# MB963.net
KiCad netlist of a schematic drawn in Altium Designer
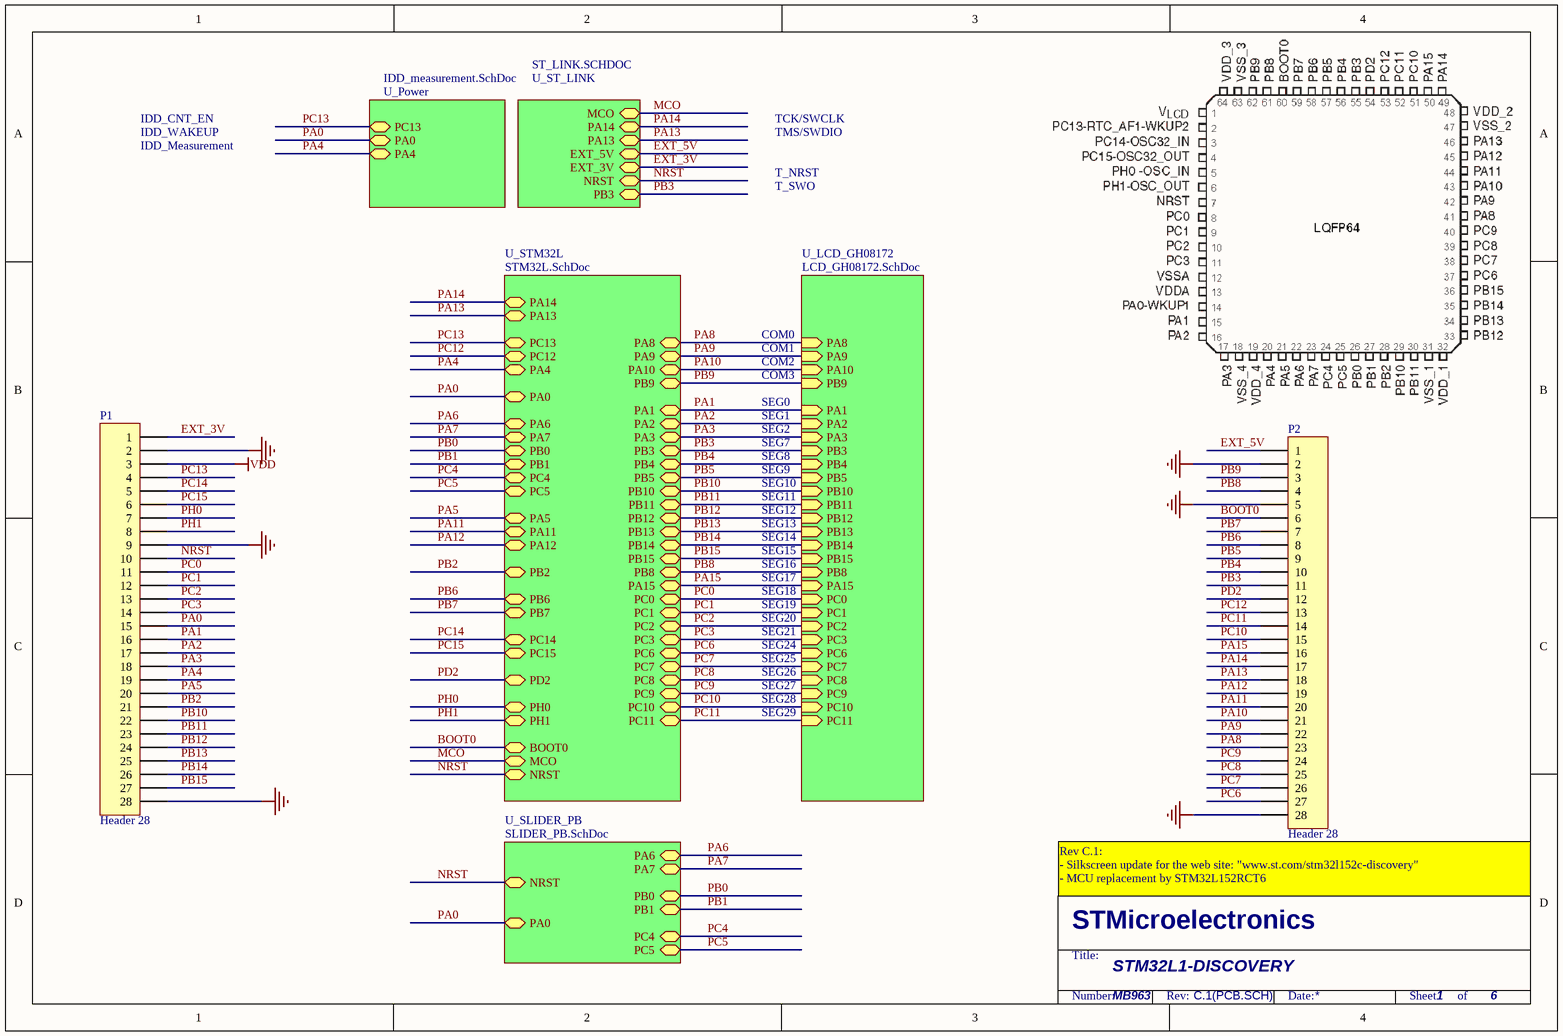
[diagram p0: MB963.SchDoc]

(export (version "E")
  (design (tool "Eeschema 10.0.6"))
  (components
    (comp (ref "P1")
      (value "Header 28")
      (footprint "HDR1X28")
      (description "Header, 28-Pin")
      (fields (field (name "PUBLISHER") "Altium Limited"))
      (libsource (lib "") (part "Header 28_1"))
    )
    (comp (ref "P2")
      (value "Header 28")
      (footprint "HDR1X28")
      (description "Header, 28-Pin")
      (fields (field (name "PUBLISHER") "Altium Limited"))
      (libsource (lib "MB913_1") (part "Header 28"))
    )
  )
  (nets
    (net (code "1") (name "/BOOT0") (class "Default")
      (node (ref "P2") (pin "6") (pinfunction "6_6") (pintype "passive"))
    )
    (net (code "2") (name "/EXT_3V") (class "Default")
      (node (ref "P1") (pin "1") (pinfunction "1_1") (pintype "passive"))
    )
    (net (code "3") (name "/EXT_5V") (class "Default")
      (node (ref "P2") (pin "1") (pinfunction "1_1") (pintype "passive"))
    )
    (net (code "5") (name "/NRST") (class "Default")
      (node (ref "P1") (pin "10") (pinfunction "10_10") (pintype "passive"))
    )
    (net (code "6") (name "/PA0") (class "Default")
      (node (ref "P1") (pin "15") (pinfunction "15_15") (pintype "passive"))
    )
    (net (code "7") (name "/PA1") (class "Default")
      (node (ref "P1") (pin "16") (pinfunction "16_16") (pintype "passive"))
    )
    (net (code "8") (name "/PA2") (class "Default")
      (node (ref "P1") (pin "17") (pinfunction "17_17") (pintype "passive"))
    )
    (net (code "9") (name "/PA3") (class "Default")
      (node (ref "P1") (pin "18") (pinfunction "18_18") (pintype "passive"))
    )
    (net (code "10") (name "/PA4") (class "Default")
      (node (ref "P1") (pin "19") (pinfunction "19_19") (pintype "passive"))
    )
    (net (code "11") (name "/PA5") (class "Default")
      (node (ref "P1") (pin "20") (pinfunction "20_20") (pintype "passive"))
    )
    (net (code "14") (name "/PA8") (class "Default")
      (node (ref "P2") (pin "23") (pinfunction "23_23") (pintype "passive"))
    )
    (net (code "15") (name "/PA9") (class "Default")
      (node (ref "P2") (pin "22") (pinfunction "22_22") (pintype "passive"))
    )
    (net (code "16") (name "/PA10") (class "Default")
      (node (ref "P2") (pin "21") (pinfunction "21_21") (pintype "passive"))
    )
    (net (code "17") (name "/PA11") (class "Default")
      (node (ref "P2") (pin "20") (pinfunction "20_20") (pintype "passive"))
    )
    (net (code "18") (name "/PA12") (class "Default")
      (node (ref "P2") (pin "19") (pinfunction "19_19") (pintype "passive"))
    )
    (net (code "19") (name "/PA13") (class "Default")
      (node (ref "P2") (pin "18") (pinfunction "18_18") (pintype "passive"))
    )
    (net (code "20") (name "/PA14") (class "Default")
      (node (ref "P2") (pin "17") (pinfunction "17_17") (pintype "passive"))
    )
    (net (code "21") (name "/PA15") (class "Default")
      (node (ref "P2") (pin "16") (pinfunction "16_16") (pintype "passive"))
    )
    (net (code "24") (name "/PB2") (class "Default")
      (node (ref "P1") (pin "21") (pinfunction "21_21") (pintype "passive"))
    )
    (net (code "25") (name "/PB3") (class "Default")
      (node (ref "P2") (pin "11") (pinfunction "11_11") (pintype "passive"))
    )
    (net (code "26") (name "/PB4") (class "Default")
      (node (ref "P2") (pin "10") (pinfunction "10_10") (pintype "passive"))
    )
    (net (code "27") (name "/PB5") (class "Default")
      (node (ref "P2") (pin "9") (pinfunction "9_9") (pintype "passive"))
    )
    (net (code "28") (name "/PB6") (class "Default")
      (node (ref "P2") (pin "8") (pinfunction "8_8") (pintype "passive"))
    )
    (net (code "29") (name "/PB7") (class "Default")
      (node (ref "P2") (pin "7") (pinfunction "7_7") (pintype "passive"))
    )
    (net (code "30") (name "/PB8") (class "Default")
      (node (ref "P2") (pin "4") (pinfunction "4_4") (pintype "passive"))
    )
    (net (code "31") (name "/PB9") (class "Default")
      (node (ref "P2") (pin "3") (pinfunction "3_3") (pintype "passive"))
    )
    (net (code "32") (name "/PB10") (class "Default")
      (node (ref "P1") (pin "22") (pinfunction "22_22") (pintype "passive"))
    )
    (net (code "33") (name "/PB11") (class "Default")
      (node (ref "P1") (pin "23") (pinfunction "23_23") (pintype "passive"))
    )
    (net (code "34") (name "/PB12") (class "Default")
      (node (ref "P1") (pin "24") (pinfunction "24_24") (pintype "passive"))
    )
    (net (code "35") (name "/PB13") (class "Default")
      (node (ref "P1") (pin "25") (pinfunction "25_25") (pintype "passive"))
    )
    (net (code "36") (name "/PB14") (class "Default")
      (node (ref "P1") (pin "26") (pinfunction "26_26") (pintype "passive"))
    )
    (net (code "37") (name "/PB15") (class "Default")
      (node (ref "P1") (pin "27") (pinfunction "27_27") (pintype "passive"))
    )
    (net (code "38") (name "/PC0") (class "Default")
      (node (ref "P1") (pin "11") (pinfunction "11_11") (pintype "passive"))
    )
    (net (code "39") (name "/PC1") (class "Default")
      (node (ref "P1") (pin "12") (pinfunction "12_12") (pintype "passive"))
    )
    (net (code "40") (name "/PC2") (class "Default")
      (node (ref "P1") (pin "13") (pinfunction "13_13") (pintype "passive"))
    )
    (net (code "41") (name "/PC3") (class "Default")
      (node (ref "P1") (pin "14") (pinfunction "14_14") (pintype "passive"))
    )
    (net (code "44") (name "/PC6") (class "Default")
      (node (ref "P2") (pin "27") (pinfunction "27_27") (pintype "passive"))
    )
    (net (code "45") (name "/PC7") (class "Default")
      (node (ref "P2") (pin "26") (pinfunction "26_26") (pintype "passive"))
    )
    (net (code "46") (name "/PC8") (class "Default")
      (node (ref "P2") (pin "25") (pinfunction "25_25") (pintype "passive"))
    )
    (net (code "47") (name "/PC9") (class "Default")
      (node (ref "P2") (pin "24") (pinfunction "24_24") (pintype "passive"))
    )
    (net (code "48") (name "/PC10") (class "Default")
      (node (ref "P2") (pin "15") (pinfunction "15_15") (pintype "passive"))
    )
    (net (code "49") (name "/PC11") (class "Default")
      (node (ref "P2") (pin "14") (pinfunction "14_14") (pintype "passive"))
    )
    (net (code "50") (name "/PC12") (class "Default")
      (node (ref "P2") (pin "13") (pinfunction "13_13") (pintype "passive"))
    )
    (net (code "51") (name "/PC13") (class "Default")
      (node (ref "P1") (pin "4") (pinfunction "4_4") (pintype "passive"))
    )
    (net (code "52") (name "/PC14") (class "Default")
      (node (ref "P1") (pin "5") (pinfunction "5_5") (pintype "passive"))
    )
    (net (code "53") (name "/PC15") (class "Default")
      (node (ref "P1") (pin "6") (pinfunction "6_6") (pintype "passive"))
    )
    (net (code "54") (name "/PD2") (class "Default")
      (node (ref "P2") (pin "12") (pinfunction "12_12") (pintype "passive"))
    )
    (net (code "55") (name "/PH0") (class "Default")
      (node (ref "P1") (pin "7") (pinfunction "7_7") (pintype "passive"))
    )
    (net (code "56") (name "/PH1") (class "Default")
      (node (ref "P1") (pin "8") (pinfunction "8_8") (pintype "passive"))
    )
    (net (code "57") (name "GND") (class "Default")
      (node (ref "P1") (pin "2") (pinfunction "2_2") (pintype "passive"))
      (node (ref "P1") (pin "28") (pinfunction "28_28") (pintype "passive"))
      (node (ref "P1") (pin "9") (pinfunction "9_9") (pintype "passive"))
      (node (ref "P2") (pin "2") (pinfunction "2_2") (pintype "passive"))
      (node (ref "P2") (pin "28") (pinfunction "28_28") (pintype "passive"))
      (node (ref "P2") (pin "5") (pinfunction "5_5") (pintype "passive"))
    )
    (net (code "58") (name "VDD") (class "Default")
      (node (ref "P1") (pin "3") (pinfunction "3_3") (pintype "passive"))
    )
  )
)
